# cosv-carrier-teensy40.net
KiCad netlist of a schematic drawn in EAGLE
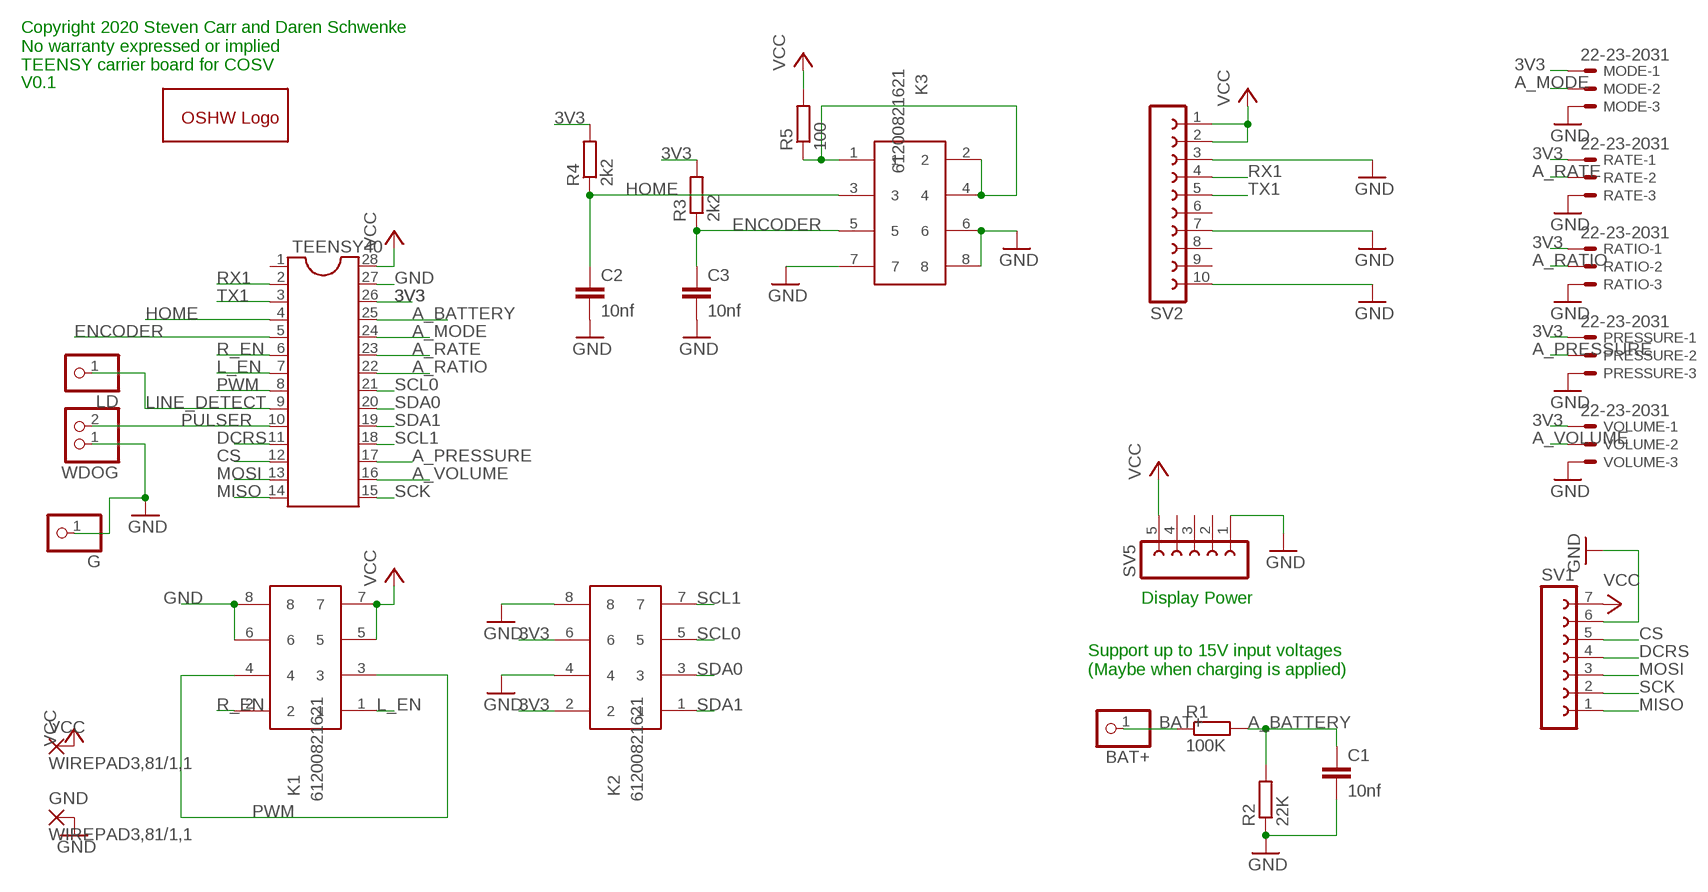
[diagram p0: schematic, sheet 1]

(export (version "E")
  (design (tool "Eeschema 10.0.6"))
  (components
    (comp (ref "BAT+")
      (value "PINHD-1X01_2.54-S")
      (footprint "eagle-import:1X01-S")
      (libsource (lib "eagle-import") (part "PINHD-1X01_2.54-S"))
    )
    (comp (ref "C1")
      (value "10nf")
      (footprint "eagle-import:C1206")
      (libsource (lib "eagle-import") (part "C-EUC1206"))
    )
    (comp (ref "C2")
      (value "10nf")
      (footprint "eagle-import:C1206")
      (libsource (lib "eagle-import") (part "C-EUC1206"))
    )
    (comp (ref "C3")
      (value "10nf")
      (footprint "eagle-import:C1206")
      (libsource (lib "eagle-import") (part "C-EUC1206"))
    )
    (comp (ref "G")
      (value "PINHD-1X01_2.54-S")
      (footprint "eagle-import:1X01-S")
      (libsource (lib "eagle-import") (part "PINHD-1X01_2.54-S"))
    )
    (comp (ref "GND")
      (value "WIREPAD3,81/1,1")
      (footprint "eagle-import:3,81_1,1")
      (libsource (lib "eagle-import") (part "WIREPAD3,81/1,1"))
    )
    (comp (ref "GOLD_ORB_SM1")
      (value "OSHWLOGOLOGO8MM")
      (footprint "eagle-import:OSHW_8MM")
      (libsource (lib "eagle-import") (part "OSHWLOGOLOGO8MM"))
    )
    (comp (ref "K1")
      (value "61200821621")
      (footprint "eagle-import:61200821621")
      (libsource (lib "eagle-import") (part "61200821621"))
    )
    (comp (ref "K2")
      (value "61200821621")
      (footprint "eagle-import:61200821621")
      (libsource (lib "eagle-import") (part "61200821621"))
    )
    (comp (ref "K3")
      (value "61200821621")
      (footprint "eagle-import:61200821621")
      (libsource (lib "eagle-import") (part "61200821621"))
    )
    (comp (ref "LD")
      (value "PINHD-1X01_2.54-S")
      (footprint "eagle-import:1X01-S")
      (libsource (lib "eagle-import") (part "PINHD-1X01_2.54-S"))
    )
    (comp (ref "MODE")
      (value "22-23-2031")
      (footprint "eagle-import:22-23-2031")
      (fields (field (name "MF") "MOLEX"))
      (libsource (lib "eagle-import") (part "22-23-2031"))
    )
    (comp (ref "PRESSURE")
      (value "22-23-2031")
      (footprint "eagle-import:22-23-2031")
      (fields (field (name "MF") "MOLEX"))
      (libsource (lib "eagle-import") (part "22-23-2031"))
    )
    (comp (ref "R1")
      (value "100K")
      (footprint "eagle-import:R1206")
      (libsource (lib "eagle-import") (part "R-EU_R1206"))
    )
    (comp (ref "R2")
      (value "22K")
      (footprint "eagle-import:R1206")
      (libsource (lib "eagle-import") (part "R-EU_R1206"))
    )
    (comp (ref "R3")
      (value "2k2")
      (footprint "eagle-import:R1206")
      (libsource (lib "eagle-import") (part "R-EU_R1206"))
    )
    (comp (ref "R4")
      (value "2k2")
      (footprint "eagle-import:R1206")
      (libsource (lib "eagle-import") (part "R-EU_R1206"))
    )
    (comp (ref "R5")
      (value "100")
      (footprint "eagle-import:R1206")
      (libsource (lib "eagle-import") (part "R-EU_R1206"))
    )
    (comp (ref "RATE")
      (value "22-23-2031")
      (footprint "eagle-import:22-23-2031")
      (fields (field (name "MF") "MOLEX"))
      (libsource (lib "eagle-import") (part "22-23-2031"))
    )
    (comp (ref "RATIO")
      (value "22-23-2031")
      (footprint "eagle-import:22-23-2031")
      (fields (field (name "MF") "MOLEX"))
      (libsource (lib "eagle-import") (part "22-23-2031"))
    )
    (comp (ref "SV1")
      (value "FE07-1")
      (footprint "eagle-import:FE07")
      (libsource (lib "eagle-import") (part "FE07-1"))
    )
    (comp (ref "SV2")
      (value "FE10-1")
      (footprint "eagle-import:FE10")
      (libsource (lib "eagle-import") (part "FE10-1"))
    )
    (comp (ref "SV5")
      (value "FE05W")
      (footprint "eagle-import:FE05W")
      (libsource (lib "eagle-import") (part "FE05W"))
    )
    (comp (ref "TEENSY40")
      (value "DIL28")
      (footprint "eagle-import:DIL28-6")
      (libsource (lib "eagle-import") (part "DIL28"))
    )
    (comp (ref "VCC")
      (value "WIREPAD3,81/1,1")
      (footprint "eagle-import:3,81_1,1")
      (libsource (lib "eagle-import") (part "WIREPAD3,81/1,1"))
    )
    (comp (ref "VOLUME")
      (value "22-23-2031")
      (footprint "eagle-import:22-23-2031")
      (fields (field (name "MF") "MOLEX"))
      (libsource (lib "eagle-import") (part "22-23-2031"))
    )
    (comp (ref "WDOG")
      (value "PINHD-1X2")
      (footprint "eagle-import:1X02")
      (libsource (lib "eagle-import") (part "PINHD-1X2"))
    )
  )
  (nets
    (net (code "1") (name "/3V3") (class "Default")
      (node (ref "K2") (pin "2") (pinfunction "2_2") (pintype "passive"))
      (node (ref "K2") (pin "6") (pinfunction "6_6") (pintype "passive"))
      (node (ref "MODE") (pin "1") (pinfunction "S_1") (pintype "passive"))
      (node (ref "PRESSURE") (pin "1") (pinfunction "S_1") (pintype "passive"))
      (node (ref "R3") (pin "2") (pinfunction "2_2") (pintype "passive"))
      (node (ref "R4") (pin "2") (pinfunction "2_2") (pintype "passive"))
      (node (ref "RATE") (pin "1") (pinfunction "S_1") (pintype "passive"))
      (node (ref "RATIO") (pin "1") (pinfunction "S_1") (pintype "passive"))
      (node (ref "TEENSY40") (pin "26") (pinfunction "26_26") (pintype "passive"))
      (node (ref "VOLUME") (pin "1") (pinfunction "S_1") (pintype "passive"))
    )
    (net (code "2") (name "/A_BATTERY") (class "Default")
      (node (ref "C1") (pin "1") (pinfunction "1_1") (pintype "passive"))
      (node (ref "R1") (pin "2") (pinfunction "2_2") (pintype "passive"))
      (node (ref "R2") (pin "2") (pinfunction "2_2") (pintype "passive"))
      (node (ref "TEENSY40") (pin "25") (pinfunction "25_25") (pintype "passive"))
    )
    (net (code "3") (name "/A_MODE") (class "Default")
      (node (ref "MODE") (pin "2") (pinfunction "S_2") (pintype "passive"))
      (node (ref "TEENSY40") (pin "24") (pinfunction "24_24") (pintype "passive"))
    )
    (net (code "4") (name "/A_PRESSURE") (class "Default")
      (node (ref "PRESSURE") (pin "2") (pinfunction "S_2") (pintype "passive"))
      (node (ref "TEENSY40") (pin "17") (pinfunction "17_17") (pintype "passive"))
    )
    (net (code "5") (name "/A_RATE") (class "Default")
      (node (ref "RATE") (pin "2") (pinfunction "S_2") (pintype "passive"))
      (node (ref "TEENSY40") (pin "23") (pinfunction "23_23") (pintype "passive"))
    )
    (net (code "6") (name "/A_RATIO") (class "Default")
      (node (ref "RATIO") (pin "2") (pinfunction "S_2") (pintype "passive"))
      (node (ref "TEENSY40") (pin "22") (pinfunction "22_22") (pintype "passive"))
    )
    (net (code "7") (name "/A_VOLUME") (class "Default")
      (node (ref "TEENSY40") (pin "16") (pinfunction "16_16") (pintype "passive"))
      (node (ref "VOLUME") (pin "2") (pinfunction "S_2") (pintype "passive"))
    )
    (net (code "8") (name "/BAT+") (class "Default")
      (node (ref "BAT+") (pin "1") (pinfunction "1_1") (pintype "passive"))
      (node (ref "R1") (pin "1") (pinfunction "1_1") (pintype "passive"))
    )
    (net (code "9") (name "/CS") (class "Default")
      (node (ref "SV1") (pin "5") (pinfunction "5_5") (pintype "passive"))
      (node (ref "TEENSY40") (pin "12") (pinfunction "12_12") (pintype "passive"))
    )
    (net (code "10") (name "/DCRS") (class "Default")
      (node (ref "SV1") (pin "4") (pinfunction "4_4") (pintype "passive"))
      (node (ref "TEENSY40") (pin "11") (pinfunction "11_11") (pintype "passive"))
    )
    (net (code "11") (name "/ENCODER") (class "Default")
      (node (ref "C3") (pin "1") (pinfunction "1_1") (pintype "passive"))
      (node (ref "K3") (pin "5") (pinfunction "5_5") (pintype "passive"))
      (node (ref "R3") (pin "1") (pinfunction "1_1") (pintype "passive"))
      (node (ref "TEENSY40") (pin "5") (pinfunction "5_5") (pintype "passive"))
    )
    (net (code "12") (name "/HOME") (class "Default")
      (node (ref "C2") (pin "1") (pinfunction "1_1") (pintype "passive"))
      (node (ref "K3") (pin "3") (pinfunction "3_3") (pintype "passive"))
      (node (ref "R4") (pin "1") (pinfunction "1_1") (pintype "passive"))
      (node (ref "TEENSY40") (pin "4") (pinfunction "4_4") (pintype "passive"))
    )
    (net (code "13") (name "/LINE_DETECT") (class "Default")
      (node (ref "LD") (pin "1") (pinfunction "1_1") (pintype "passive"))
      (node (ref "TEENSY40") (pin "9") (pinfunction "9_9") (pintype "passive"))
    )
    (net (code "14") (name "/L_EN") (class "Default")
      (node (ref "K1") (pin "1") (pinfunction "1_1") (pintype "passive"))
      (node (ref "TEENSY40") (pin "7") (pinfunction "7_7") (pintype "passive"))
    )
    (net (code "15") (name "/MISO") (class "Default")
      (node (ref "SV1") (pin "1") (pinfunction "1_1") (pintype "passive"))
      (node (ref "TEENSY40") (pin "14") (pinfunction "14_14") (pintype "passive"))
    )
    (net (code "16") (name "/MOSI") (class "Default")
      (node (ref "SV1") (pin "3") (pinfunction "3_3") (pintype "passive"))
      (node (ref "TEENSY40") (pin "13") (pinfunction "13_13") (pintype "passive"))
    )
    (net (code "17") (name "/PULSER") (class "Default")
      (node (ref "TEENSY40") (pin "10") (pinfunction "10_10") (pintype "passive"))
      (node (ref "WDOG") (pin "2") (pinfunction "2_2") (pintype "passive"))
    )
    (net (code "18") (name "/PWM") (class "Default")
      (node (ref "K1") (pin "3") (pinfunction "3_3") (pintype "passive"))
      (node (ref "K1") (pin "4") (pinfunction "4_4") (pintype "passive"))
      (node (ref "TEENSY40") (pin "8") (pinfunction "8_8") (pintype "passive"))
    )
    (net (code "19") (name "/RX1") (class "Default")
      (node (ref "SV2") (pin "4") (pinfunction "4_4") (pintype "passive"))
      (node (ref "TEENSY40") (pin "2") (pinfunction "2_2") (pintype "passive"))
    )
    (net (code "20") (name "/R_EN") (class "Default")
      (node (ref "K1") (pin "2") (pinfunction "2_2") (pintype "passive"))
      (node (ref "TEENSY40") (pin "6") (pinfunction "6_6") (pintype "passive"))
    )
    (net (code "21") (name "/SCK") (class "Default")
      (node (ref "SV1") (pin "2") (pinfunction "2_2") (pintype "passive"))
      (node (ref "TEENSY40") (pin "15") (pinfunction "15_15") (pintype "passive"))
    )
    (net (code "22") (name "/SCL0") (class "Default")
      (node (ref "K2") (pin "5") (pinfunction "5_5") (pintype "passive"))
      (node (ref "TEENSY40") (pin "21") (pinfunction "21_21") (pintype "passive"))
    )
    (net (code "23") (name "/SCL1") (class "Default")
      (node (ref "K2") (pin "7") (pinfunction "7_7") (pintype "passive"))
      (node (ref "TEENSY40") (pin "18") (pinfunction "18_18") (pintype "passive"))
    )
    (net (code "24") (name "/SDA0") (class "Default")
      (node (ref "K2") (pin "3") (pinfunction "3_3") (pintype "passive"))
      (node (ref "TEENSY40") (pin "20") (pinfunction "20_20") (pintype "passive"))
    )
    (net (code "25") (name "/SDA1") (class "Default")
      (node (ref "K2") (pin "1") (pinfunction "1_1") (pintype "passive"))
      (node (ref "TEENSY40") (pin "19") (pinfunction "19_19") (pintype "passive"))
    )
    (net (code "26") (name "/TX1") (class "Default")
      (node (ref "SV2") (pin "5") (pinfunction "5_5") (pintype "passive"))
      (node (ref "TEENSY40") (pin "3") (pinfunction "3_3") (pintype "passive"))
    )
    (net (code "27") (name "GND") (class "Default")
      (node (ref "C1") (pin "2") (pinfunction "2_2") (pintype "passive"))
      (node (ref "C2") (pin "2") (pinfunction "2_2") (pintype "passive"))
      (node (ref "C3") (pin "2") (pinfunction "2_2") (pintype "passive"))
      (node (ref "G") (pin "1") (pinfunction "1_1") (pintype "passive"))
      (node (ref "GND") (pin "1") (pinfunction "P_1") (pintype "passive"))
      (node (ref "K1") (pin "6") (pinfunction "6_6") (pintype "passive"))
      (node (ref "K1") (pin "8") (pinfunction "8_8") (pintype "passive"))
      (node (ref "K2") (pin "4") (pinfunction "4_4") (pintype "passive"))
      (node (ref "K2") (pin "8") (pinfunction "8_8") (pintype "passive"))
      (node (ref "K3") (pin "6") (pinfunction "6_6") (pintype "passive"))
      (node (ref "K3") (pin "7") (pinfunction "7_7") (pintype "passive"))
      (node (ref "K3") (pin "8") (pinfunction "8_8") (pintype "passive"))
      (node (ref "MODE") (pin "3") (pinfunction "S_3") (pintype "passive"))
      (node (ref "PRESSURE") (pin "3") (pinfunction "S_3") (pintype "passive"))
      (node (ref "R2") (pin "1") (pinfunction "1_1") (pintype "passive"))
      (node (ref "RATE") (pin "3") (pinfunction "S_3") (pintype "passive"))
      (node (ref "RATIO") (pin "3") (pinfunction "S_3") (pintype "passive"))
      (node (ref "SV1") (pin "6") (pinfunction "6_6") (pintype "passive"))
      (node (ref "SV2") (pin "10") (pinfunction "10_10") (pintype "passive"))
      (node (ref "SV2") (pin "3") (pinfunction "3_3") (pintype "passive"))
      (node (ref "SV2") (pin "7") (pinfunction "7_7") (pintype "passive"))
      (node (ref "SV5") (pin "1") (pinfunction "1_1") (pintype "passive"))
      (node (ref "TEENSY40") (pin "27") (pinfunction "27_27") (pintype "passive"))
      (node (ref "VOLUME") (pin "3") (pinfunction "S_3") (pintype "passive"))
      (node (ref "WDOG") (pin "1") (pinfunction "1_1") (pintype "passive"))
    )
    (net (code "28") (name "Net-(K3-Pad1)") (class "Default")
      (node (ref "K3") (pin "1") (pinfunction "1_1") (pintype "passive"))
      (node (ref "K3") (pin "2") (pinfunction "2_2") (pintype "passive"))
      (node (ref "K3") (pin "4") (pinfunction "4_4") (pintype "passive"))
      (node (ref "R5") (pin "1") (pinfunction "1_1") (pintype "passive"))
    )
    (net (code "29") (name "VCC") (class "Default")
      (node (ref "K1") (pin "5") (pinfunction "5_5") (pintype "passive"))
      (node (ref "K1") (pin "7") (pinfunction "7_7") (pintype "passive"))
      (node (ref "R5") (pin "2") (pinfunction "2_2") (pintype "passive"))
      (node (ref "SV1") (pin "7") (pinfunction "7_7") (pintype "passive"))
      (node (ref "SV2") (pin "1") (pinfunction "1_1") (pintype "passive"))
      (node (ref "SV2") (pin "2") (pinfunction "2_2") (pintype "passive"))
      (node (ref "SV5") (pin "5") (pinfunction "5_5") (pintype "passive"))
      (node (ref "TEENSY40") (pin "28") (pinfunction "28_28") (pintype "passive"))
      (node (ref "VCC") (pin "1") (pinfunction "P_1") (pintype "passive"))
    )
    (net (code "30") (name "unconnected-(SV2-Pad6)") (class "Default")
      (node (ref "SV2") (pin "6") (pinfunction "6_6") (pintype "passive"))
    )
    (net (code "31") (name "unconnected-(SV2-Pad8)") (class "Default")
      (node (ref "SV2") (pin "8") (pinfunction "8_8") (pintype "passive"))
    )
    (net (code "32") (name "unconnected-(SV2-Pad9)") (class "Default")
      (node (ref "SV2") (pin "9") (pinfunction "9_9") (pintype "passive"))
    )
    (net (code "33") (name "unconnected-(SV5-Pad2)") (class "Default")
      (node (ref "SV5") (pin "2") (pinfunction "2_2") (pintype "passive"))
    )
    (net (code "34") (name "unconnected-(SV5-Pad3)") (class "Default")
      (node (ref "SV5") (pin "3") (pinfunction "3_3") (pintype "passive"))
    )
    (net (code "35") (name "unconnected-(SV5-Pad4)") (class "Default")
      (node (ref "SV5") (pin "4") (pinfunction "4_4") (pintype "passive"))
    )
    (net (code "36") (name "unconnected-(TEENSY40-Pad1)") (class "Default")
      (node (ref "TEENSY40") (pin "1") (pinfunction "1_1") (pintype "passive"))
    )
  )
)
